# IO.net
KiCad netlist of a schematic drawn in Altium Designer
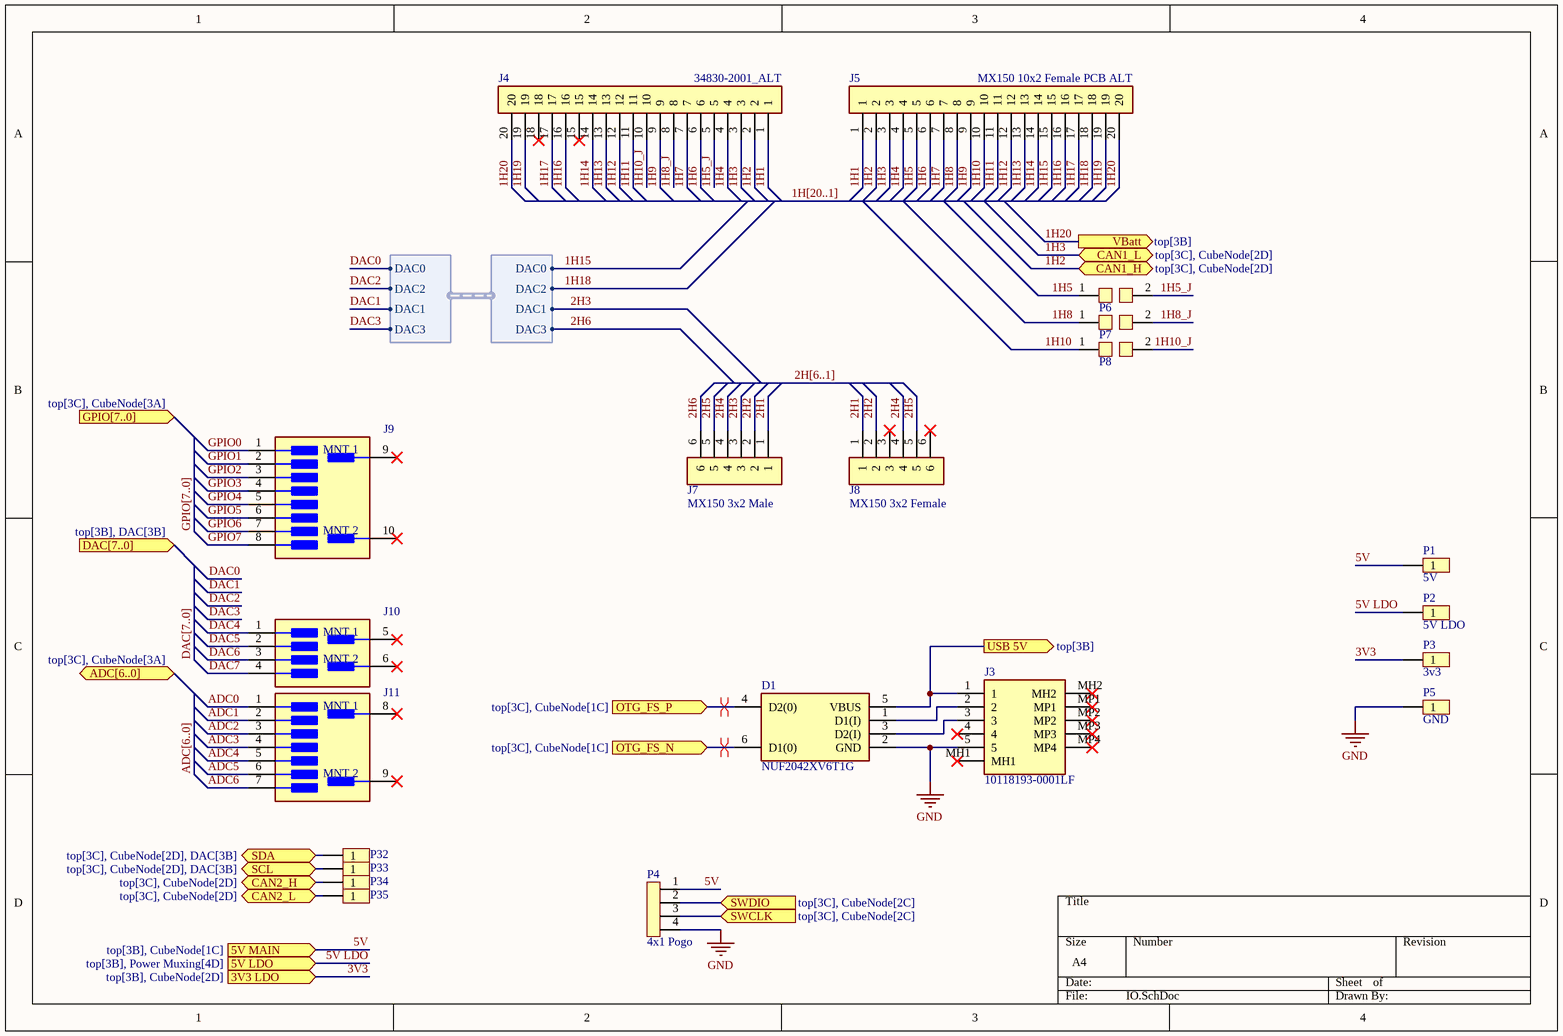
[diagram p0: IO.SchDoc]

(export (version "E")
  (design (tool "Eeschema 10.0.6"))
  (components
    (comp (ref "D1")
      (value "NUF2042XV6T1G")
      (footprint "SamacSys:SOTFL50P160X60-6N")
      (description "Diode")
      (fields (field (name "MOUSER PART NUMBER") "863-NUF2042XV6T1G"))
      (libsource (lib "SamacSys") (part "NUF2042XV6T1G"))
    )
    (comp (ref "J3")
      (value "10118193-0001LF")
      (footprint "SamacSys:101181930001LF")
      (description "Connector")
      (libsource (lib "*") (part "10118193-0001LF"))
    )
    (comp (ref "J4")
      (value "34830-2001_ALT")
      (footprint "MOLEX_MX150:348302001")
      (description "Connector")
      (fields
        (field (name "MANUFACTURER_PART_NUMBER") "34830-2001")
        (field (name "MOUSER PART NUMBER") "538-34830-2001")
      )
      (libsource (lib "MOLEX_MX150") (part "34830-2001_ALT"))
    )
    (comp (ref "J5")
      (value "MX150 10x2 Female PCB ALT")
      (footprint "MOLEX_MX150:348302001")
      (description "Connector")
      (fields
        (field (name "MANUFACTURER_PART_NUMBER") "34830-2001")
        (field (name "MOUSER PART NUMBER") "538-34830-2001")
      )
      (libsource (lib "MOLEX_MX150") (part "MX150 10x2 Female PCB ALT"))
    )
    (comp (ref "J7")
      (value "MX150 3x2 Male")
      (footprint "MOLEX_MX150:348302001")
      (description "Connector")
      (fields
        (field (name "MANUFACTURER_PART_NUMBER") "34830-2001")
        (field (name "MOUSER PART NUMBER") "538-34830-2001")
      )
      (libsource (lib "MOLEX_MX150") (part "MX150 3x2 Male PCB ALT"))
    )
    (comp (ref "J8")
      (value "MX150 3x2 Female")
      (footprint "MOLEX_MX150:348302001")
      (description "Connector")
      (fields
        (field (name "MANUFACTURER_PART_NUMBER") "34830-2001")
        (field (name "MOUSER PART NUMBER") "538-34830-2001")
      )
      (libsource (lib "MOLEX_MX150") (part "MX150 3x2 Female PCB ALT"))
    )
    (comp (ref "J9")
      (value "BM08B-GHS-TBT(LF)(SN)")
      (footprint "FP-BM08B-GHS-TBT_LF_SN-MFG")
      (description "CONN HEADER SMD 8POS 1.25MM")
      (libsource (lib "JST-GH") (part "BM08B-GHS-TBT(LF)(SN)"))
    )
    (comp (ref "J10")
      (value "BM04B-GHS-TBT(LF)(SN)(N)")
      (footprint "FP-BM04B-GHS-TBT_LF_SN-MFG")
      (description "CONN HEADER SMD 4POS 1.25MM")
      (libsource (lib "JST-GH") (part "BM04B-GHS-TBT(LF)(SN)(N)"))
    )
    (comp (ref "J11")
      (value "BM07B-GHS-TBT (LF)(SN)")
      (footprint "FP-BM07B-GHS-TBT_LF_SN-MFG")
      (description "CONN HEADER SMD 7POS 1.25MM")
      (libsource (lib "JST-GH") (part "CMP-17439-000607-1"))
    )
    (comp (ref "P1")
      (value "5V")
      (footprint "Test Point")
      (libsource (lib "Generic_Pads") (part "Test Point"))
    )
    (comp (ref "P2")
      (value "5V LDO")
      (footprint "Test Point")
      (libsource (lib "Generic_Pads") (part "Test Point"))
    )
    (comp (ref "P3")
      (value "3v3")
      (footprint "Test Point")
      (libsource (lib "Generic_Pads") (part "Test Point"))
    )
    (comp (ref "P4")
      (value "4x1 Pogo")
      (footprint "POGO4x1")
      (libsource (lib "Generic_Pads") (part "4x1 Pogo"))
    )
    (comp (ref "P5")
      (value "GND")
      (footprint "Test Point")
      (libsource (lib "Generic_Pads") (part "Test Point"))
    )
    (comp (ref "P6")
      (value "SPST Jumper")
      (footprint "SPST Solder Jumper")
      (libsource (lib "Generic_Pads") (part "SPST Jumper"))
    )
    (comp (ref "P7")
      (value "SPST Jumper")
      (footprint "SPST Solder Jumper")
      (libsource (lib "Generic_Pads") (part "SPST Jumper"))
    )
    (comp (ref "P8")
      (value "SPST Jumper")
      (footprint "SPST Solder Jumper")
      (libsource (lib "Generic_Pads") (part "SPST Jumper"))
    )
    (comp (ref "P32")
      (value "Test Point")
      (footprint "Test Point")
      (libsource (lib "") (part "Test Point_1"))
    )
    (comp (ref "P33")
      (value "Test Point")
      (footprint "Test Point")
      (libsource (lib "") (part "Test Point_1"))
    )
    (comp (ref "P34")
      (value "Test Point")
      (footprint "Test Point")
      (libsource (lib "") (part "Test Point_1"))
    )
    (comp (ref "P35")
      (value "Test Point")
      (footprint "Test Point")
      (libsource (lib "") (part "Test Point_1"))
    )
  )
  (nets
    (net (code "2") (name "/1H1") (class "Default")
      (node (ref "J4") (pin "1") (pinfunction "1_1") (pintype "passive"))
      (node (ref "J5") (pin "1") (pinfunction "1_1") (pintype "passive"))
    )
    (net (code "3") (name "/1H2") (class "Default")
      (node (ref "J4") (pin "2") (pinfunction "2_2") (pintype "passive"))
      (node (ref "J5") (pin "2") (pinfunction "2_2") (pintype "passive"))
    )
    (net (code "4") (name "/1H3") (class "Default")
      (node (ref "J4") (pin "3") (pinfunction "3_3") (pintype "passive"))
      (node (ref "J5") (pin "3") (pinfunction "3_3") (pintype "passive"))
    )
    (net (code "5") (name "/1H4") (class "Default")
      (node (ref "J4") (pin "4") (pinfunction "4_4") (pintype "passive"))
      (node (ref "J5") (pin "4") (pinfunction "4_4") (pintype "passive"))
    )
    (net (code "6") (name "/1H5") (class "Default")
      (node (ref "J5") (pin "5") (pinfunction "5_5") (pintype "passive"))
      (node (ref "P6") (pin "1") (pinfunction "1_1") (pintype "passive"))
    )
    (net (code "7") (name "/1H5_J") (class "Default")
      (node (ref "J4") (pin "5") (pinfunction "5_5") (pintype "passive"))
      (node (ref "P6") (pin "2") (pinfunction "2_2") (pintype "passive"))
    )
    (net (code "8") (name "/1H6") (class "Default")
      (node (ref "J4") (pin "6") (pinfunction "6_6") (pintype "passive"))
      (node (ref "J5") (pin "6") (pinfunction "6_6") (pintype "passive"))
    )
    (net (code "9") (name "/1H7") (class "Default")
      (node (ref "J4") (pin "7") (pinfunction "7_7") (pintype "passive"))
      (node (ref "J5") (pin "7") (pinfunction "7_7") (pintype "passive"))
    )
    (net (code "10") (name "/1H8") (class "Default")
      (node (ref "J5") (pin "8") (pinfunction "8_8") (pintype "passive"))
      (node (ref "P7") (pin "1") (pinfunction "1_1") (pintype "passive"))
    )
    (net (code "11") (name "/1H8_J") (class "Default")
      (node (ref "J4") (pin "8") (pinfunction "8_8") (pintype "passive"))
      (node (ref "P7") (pin "2") (pinfunction "2_2") (pintype "passive"))
    )
    (net (code "12") (name "/1H9") (class "Default")
      (node (ref "J4") (pin "9") (pinfunction "9_9") (pintype "passive"))
      (node (ref "J5") (pin "9") (pinfunction "9_9") (pintype "passive"))
    )
    (net (code "13") (name "/1H10") (class "Default")
      (node (ref "J5") (pin "10") (pinfunction "10_10") (pintype "passive"))
      (node (ref "P8") (pin "1") (pinfunction "1_1") (pintype "passive"))
    )
    (net (code "14") (name "/1H10_J") (class "Default")
      (node (ref "J4") (pin "10") (pinfunction "10_10") (pintype "passive"))
      (node (ref "P8") (pin "2") (pinfunction "2_2") (pintype "passive"))
    )
    (net (code "15") (name "/1H11") (class "Default")
      (node (ref "J4") (pin "11") (pinfunction "11_11") (pintype "passive"))
      (node (ref "J5") (pin "11") (pinfunction "11_11") (pintype "passive"))
    )
    (net (code "16") (name "/1H12") (class "Default")
      (node (ref "J4") (pin "12") (pinfunction "12_12") (pintype "passive"))
      (node (ref "J5") (pin "12") (pinfunction "12_12") (pintype "passive"))
    )
    (net (code "17") (name "/1H13") (class "Default")
      (node (ref "J4") (pin "13") (pinfunction "13_13") (pintype "passive"))
      (node (ref "J5") (pin "13") (pinfunction "13_13") (pintype "passive"))
    )
    (net (code "18") (name "/1H14") (class "Default")
      (node (ref "J4") (pin "14") (pinfunction "14_14") (pintype "passive"))
      (node (ref "J5") (pin "14") (pinfunction "14_14") (pintype "passive"))
    )
    (net (code "19") (name "/1H15") (class "Default")
      (node (ref "J5") (pin "15") (pinfunction "15_15") (pintype "passive"))
    )
    (net (code "20") (name "/1H16") (class "Default")
      (node (ref "J4") (pin "16") (pinfunction "16_16") (pintype "passive"))
      (node (ref "J5") (pin "16") (pinfunction "16_16") (pintype "passive"))
    )
    (net (code "21") (name "/1H17") (class "Default")
      (node (ref "J4") (pin "17") (pinfunction "17_17") (pintype "passive"))
      (node (ref "J5") (pin "17") (pinfunction "17_17") (pintype "passive"))
    )
    (net (code "22") (name "/1H18") (class "Default")
      (node (ref "J5") (pin "18") (pinfunction "18_18") (pintype "passive"))
    )
    (net (code "23") (name "/1H19") (class "Default")
      (node (ref "J4") (pin "19") (pinfunction "19_19") (pintype "passive"))
      (node (ref "J5") (pin "19") (pinfunction "19_19") (pintype "passive"))
    )
    (net (code "24") (name "/1H20") (class "Default")
      (node (ref "J4") (pin "20") (pinfunction "20_20") (pintype "passive"))
      (node (ref "J5") (pin "20") (pinfunction "20_20") (pintype "passive"))
    )
    (net (code "26") (name "/2H1") (class "Default")
      (node (ref "J7") (pin "1") (pinfunction "1_1") (pintype "passive"))
      (node (ref "J8") (pin "1") (pinfunction "1_1") (pintype "passive"))
    )
    (net (code "27") (name "/2H2") (class "Default")
      (node (ref "J7") (pin "2") (pinfunction "2_2") (pintype "passive"))
      (node (ref "J8") (pin "2") (pinfunction "2_2") (pintype "passive"))
    )
    (net (code "28") (name "/2H3") (class "Default")
      (node (ref "J7") (pin "3") (pinfunction "3_3") (pintype "passive"))
    )
    (net (code "29") (name "/2H4") (class "Default")
      (node (ref "J7") (pin "4") (pinfunction "4_4") (pintype "passive"))
      (node (ref "J8") (pin "4") (pinfunction "4_4") (pintype "passive"))
    )
    (net (code "30") (name "/2H5") (class "Default")
      (node (ref "J7") (pin "5") (pinfunction "5_5") (pintype "passive"))
      (node (ref "J8") (pin "5") (pinfunction "5_5") (pintype "passive"))
    )
    (net (code "31") (name "/2H6") (class "Default")
      (node (ref "J7") (pin "6") (pinfunction "6_6") (pintype "passive"))
    )
    (net (code "33") (name "/3V3") (class "Default")
      (node (ref "P3") (pin "1") (pinfunction "1_1") (pintype "passive"))
    )
    (net (code "34") (name "/5V") (class "Default")
      (node (ref "P1") (pin "1") (pinfunction "1_1") (pintype "passive"))
      (node (ref "P4") (pin "1") (pinfunction "1_1") (pintype "passive"))
    )
    (net (code "35") (name "/5V LDO") (class "Default")
      (node (ref "P2") (pin "1") (pinfunction "1_1") (pintype "passive"))
    )
    (net (code "36") (name "/ADC0") (class "Default")
      (node (ref "J11") (pin "1") (pinfunction "1_1") (pintype "passive"))
    )
    (net (code "37") (name "/ADC1") (class "Default")
      (node (ref "J11") (pin "2") (pinfunction "2_2") (pintype "passive"))
    )
    (net (code "38") (name "/ADC2") (class "Default")
      (node (ref "J11") (pin "3") (pinfunction "3_3") (pintype "passive"))
    )
    (net (code "39") (name "/ADC3") (class "Default")
      (node (ref "J11") (pin "4") (pinfunction "4_4") (pintype "passive"))
    )
    (net (code "40") (name "/ADC4") (class "Default")
      (node (ref "J11") (pin "5") (pinfunction "5_5") (pintype "passive"))
    )
    (net (code "41") (name "/ADC5") (class "Default")
      (node (ref "J11") (pin "6") (pinfunction "6_6") (pintype "passive"))
    )
    (net (code "42") (name "/ADC6") (class "Default")
      (node (ref "J11") (pin "7") (pinfunction "7_7") (pintype "passive"))
    )
    (net (code "44") (name "/CAN2_H") (class "Default")
      (node (ref "P34") (pin "1") (pinfunction "1_1") (pintype "passive"))
    )
    (net (code "45") (name "/CAN2_L") (class "Default")
      (node (ref "P35") (pin "1") (pinfunction "1_1") (pintype "passive"))
    )
    (net (code "50") (name "/DAC4") (class "Default")
      (node (ref "J10") (pin "1") (pinfunction "1_1") (pintype "passive"))
    )
    (net (code "51") (name "/DAC5") (class "Default")
      (node (ref "J10") (pin "2") (pinfunction "2_2") (pintype "passive"))
    )
    (net (code "52") (name "/DAC6") (class "Default")
      (node (ref "J10") (pin "3") (pinfunction "3_3") (pintype "passive"))
    )
    (net (code "53") (name "/DAC7") (class "Default")
      (node (ref "J10") (pin "4") (pinfunction "4_4") (pintype "passive"))
    )
    (net (code "55") (name "/GPIO0") (class "Default")
      (node (ref "J9") (pin "1") (pinfunction "1_1") (pintype "passive"))
    )
    (net (code "56") (name "/GPIO1") (class "Default")
      (node (ref "J9") (pin "2") (pinfunction "2_2") (pintype "passive"))
    )
    (net (code "57") (name "/GPIO2") (class "Default")
      (node (ref "J9") (pin "3") (pinfunction "3_3") (pintype "passive"))
    )
    (net (code "58") (name "/GPIO3") (class "Default")
      (node (ref "J9") (pin "4") (pinfunction "4_4") (pintype "passive"))
    )
    (net (code "59") (name "/GPIO4") (class "Default")
      (node (ref "J9") (pin "5") (pinfunction "5_5") (pintype "passive"))
    )
    (net (code "60") (name "/GPIO5") (class "Default")
      (node (ref "J9") (pin "6") (pinfunction "6_6") (pintype "passive"))
    )
    (net (code "61") (name "/GPIO6") (class "Default")
      (node (ref "J9") (pin "7") (pinfunction "7_7") (pintype "passive"))
    )
    (net (code "62") (name "/GPIO7") (class "Default")
      (node (ref "J9") (pin "8") (pinfunction "8_8") (pintype "passive"))
    )
    (net (code "64") (name "/OTG_FS_N") (class "Default")
      (node (ref "D1") (pin "6") (pinfunction "D1(0)_6") (pintype "passive"))
    )
    (net (code "65") (name "/OTG_FS_P") (class "Default")
      (node (ref "D1") (pin "4") (pinfunction "D2(0)_4") (pintype "passive"))
    )
    (net (code "66") (name "/SCL") (class "Default")
      (node (ref "P33") (pin "1") (pinfunction "1_1") (pintype "passive"))
    )
    (net (code "67") (name "/SDA") (class "Default")
      (node (ref "P32") (pin "1") (pinfunction "1_1") (pintype "passive"))
    )
    (net (code "68") (name "/SWCLK") (class "Default")
      (node (ref "P4") (pin "3") (pinfunction "3_3") (pintype "passive"))
    )
    (net (code "69") (name "/SWDIO") (class "Default")
      (node (ref "P4") (pin "2") (pinfunction "2_2") (pintype "passive"))
    )
    (net (code "70") (name "/USB 5V") (class "Default")
      (node (ref "D1") (pin "5") (pinfunction "VBUS_5") (pintype "passive"))
      (node (ref "J3") (pin "1") (pinfunction "1_1") (pintype "passive"))
    )
    (net (code "72") (name "GND") (class "Default")
      (node (ref "D1") (pin "2") (pinfunction "GND_2") (pintype "passive"))
      (node (ref "J3") (pin "5") (pinfunction "5_5") (pintype "passive"))
      (node (ref "P4") (pin "4") (pinfunction "4_4") (pintype "passive"))
      (node (ref "P5") (pin "1") (pinfunction "1_1") (pintype "passive"))
    )
    (net (code "73") (name "Net-(D1-D1(I))") (class "Default")
      (node (ref "D1") (pin "1") (pinfunction "D1(I)_1") (pintype "passive"))
      (node (ref "J3") (pin "2") (pinfunction "2_2") (pintype "passive"))
    )
    (net (code "74") (name "Net-(D1-D2(I))") (class "Default")
      (node (ref "D1") (pin "3") (pinfunction "D2(I)_3") (pintype "passive"))
      (node (ref "J3") (pin "3") (pinfunction "3_3") (pintype "passive"))
    )
    (net (code "75") (name "unconnected-(J3-Pad4)") (class "Default")
      (node (ref "J3") (pin "4") (pinfunction "4_4") (pintype "passive+no_connect"))
    )
    (net (code "76") (name "unconnected-(J3-PadMH1)") (class "Default")
      (node (ref "J3") (pin "MH1") (pinfunction "MH1_MH1") (pintype "passive+no_connect"))
    )
    (net (code "77") (name "unconnected-(J3-PadMH2)") (class "Default")
      (node (ref "J3") (pin "MH2") (pinfunction "MH2_MH2") (pintype "passive+no_connect"))
    )
    (net (code "78") (name "unconnected-(J3-PadMP1)") (class "Default")
      (node (ref "J3") (pin "MP1") (pinfunction "MP1_MP1") (pintype "passive+no_connect"))
    )
    (net (code "79") (name "unconnected-(J3-PadMP2)") (class "Default")
      (node (ref "J3") (pin "MP2") (pinfunction "MP2_MP2") (pintype "passive+no_connect"))
    )
    (net (code "80") (name "unconnected-(J3-PadMP3)") (class "Default")
      (node (ref "J3") (pin "MP3") (pinfunction "MP3_MP3") (pintype "passive+no_connect"))
    )
    (net (code "81") (name "unconnected-(J3-PadMP4)") (class "Default")
      (node (ref "J3") (pin "MP4") (pinfunction "MP4_MP4") (pintype "passive+no_connect"))
    )
    (net (code "82") (name "unconnected-(J4-Pad15)") (class "Default")
      (node (ref "J4") (pin "15") (pinfunction "15_15") (pintype "passive+no_connect"))
    )
    (net (code "83") (name "unconnected-(J4-Pad18)") (class "Default")
      (node (ref "J4") (pin "18") (pinfunction "18_18") (pintype "passive+no_connect"))
    )
    (net (code "84") (name "unconnected-(J8-Pad3)") (class "Default")
      (node (ref "J8") (pin "3") (pinfunction "3_3") (pintype "passive+no_connect"))
    )
    (net (code "85") (name "unconnected-(J8-Pad6)") (class "Default")
      (node (ref "J8") (pin "6") (pinfunction "6_6") (pintype "passive+no_connect"))
    )
    (net (code "86") (name "unconnected-(J9-MNT_1-Pad9)") (class "Default")
      (node (ref "J9") (pin "9") (pinfunction "MNT_1_9") (pintype "passive+no_connect"))
    )
    (net (code "87") (name "unconnected-(J9-MNT_2-Pad10)") (class "Default")
      (node (ref "J9") (pin "10") (pinfunction "MNT_2_10") (pintype "passive+no_connect"))
    )
    (net (code "88") (name "unconnected-(J10-MNT_1-Pad5)") (class "Default")
      (node (ref "J10") (pin "5") (pinfunction "MNT_1_5") (pintype "passive+no_connect"))
    )
    (net (code "89") (name "unconnected-(J10-MNT_2-Pad6)") (class "Default")
      (node (ref "J10") (pin "6") (pinfunction "MNT_2_6") (pintype "passive+no_connect"))
    )
    (net (code "90") (name "unconnected-(J11-MNT_1-Pad8)") (class "Default")
      (node (ref "J11") (pin "8") (pinfunction "MNT_1_8") (pintype "passive+no_connect"))
    )
    (net (code "91") (name "unconnected-(J11-MNT_2-Pad9)") (class "Default")
      (node (ref "J11") (pin "9") (pinfunction "MNT_2_9") (pintype "passive+no_connect"))
    )
  )
)
